# PE01.net
KiCad netlist of a schematic drawn in EAGLE
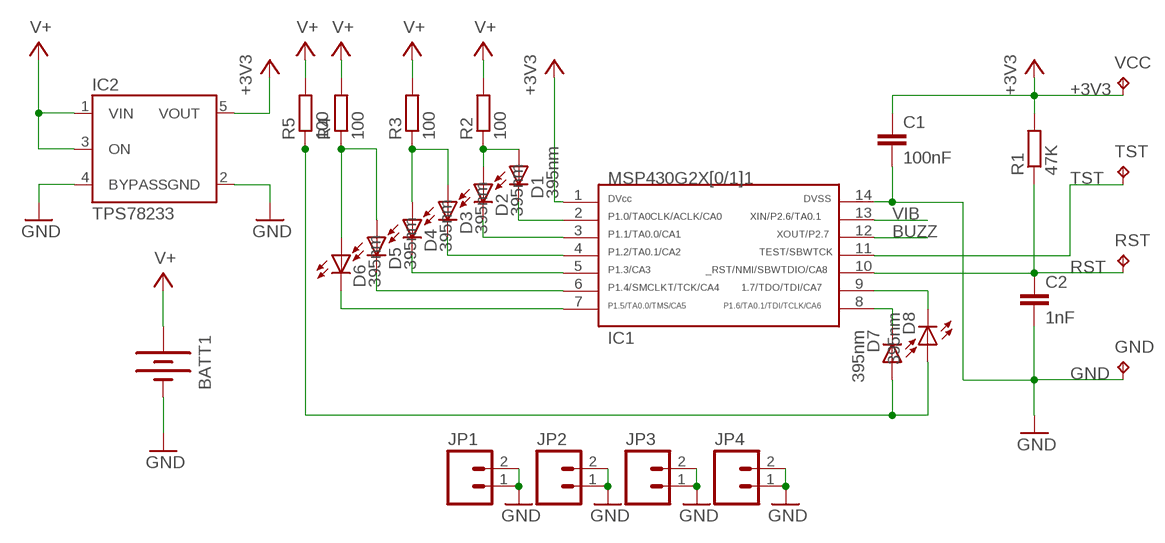
[diagram p0: schematic, sheet 1]

(export (version "E")
  (design (tool "Eeschema 10.0.6"))
  (components
    (comp (ref "BATT1")
      (value "BATTERY20MM_4LEGS")
      (footprint "eagle-import:BATTCON_20MM_4LEGS")
      (libsource (lib "eagle-import") (part "BATTERY20MM_4LEGS"))
    )
    (comp (ref "C1")
      (value "100nF")
      (footprint "eagle-import:0805")
      (libsource (lib "eagle-import") (part "CAP0805"))
    )
    (comp (ref "C2")
      (value "1nF")
      (footprint "eagle-import:0805")
      (libsource (lib "eagle-import") (part "CAP0805"))
    )
    (comp (ref "D1")
      (value "395nm")
      (footprint "eagle-import:LED-805")
      (libsource (lib "eagle-import") (part "LED-0805"))
    )
    (comp (ref "D2")
      (value "395nm")
      (footprint "eagle-import:LED-805")
      (libsource (lib "eagle-import") (part "LED-0805"))
    )
    (comp (ref "D3")
      (value "395nm")
      (footprint "eagle-import:LED-805")
      (libsource (lib "eagle-import") (part "LED-0805"))
    )
    (comp (ref "D4")
      (value "395nm")
      (footprint "eagle-import:LED-805")
      (libsource (lib "eagle-import") (part "LED-0805"))
    )
    (comp (ref "D5")
      (value "395nm")
      (footprint "eagle-import:LED-805")
      (libsource (lib "eagle-import") (part "LED-0805"))
    )
    (comp (ref "D6")
      (value "395nm")
      (footprint "eagle-import:LED-805")
      (libsource (lib "eagle-import") (part "LED-0805"))
    )
    (comp (ref "D7")
      (value "395nm")
      (footprint "eagle-import:LED-805")
      (libsource (lib "eagle-import") (part "LED-0805"))
    )
    (comp (ref "D8")
      (value "395nm")
      (footprint "eagle-import:LED-805")
      (libsource (lib "eagle-import") (part "LED-0805"))
    )
    (comp (ref "GND")
      (value "TPTP10R")
      (footprint "eagle-import:TP10R")
      (libsource (lib "eagle-import") (part "TPTP10R"))
    )
    (comp (ref "IC1")
      (value "MSP430G2231")
      (footprint "eagle-import:PW14")
      (libsource (lib "eagle-import") (part "G2X[0/1]1---PW14"))
    )
    (comp (ref "IC2")
      (value "TPS78233")
      (footprint "eagle-import:SOT23-5")
      (libsource (lib "eagle-import") (part "LP2982M5"))
    )
    (comp (ref "JP1")
      (value "M021X02_NO_SILK")
      (footprint "eagle-import:1X02_NO_SILK")
      (libsource (lib "eagle-import") (part "M021X02_NO_SILK"))
    )
    (comp (ref "JP2")
      (value "M021X02_NO_SILK")
      (footprint "eagle-import:1X02_NO_SILK")
      (libsource (lib "eagle-import") (part "M021X02_NO_SILK"))
    )
    (comp (ref "JP3")
      (value "M021X02_NO_SILK")
      (footprint "eagle-import:1X02_NO_SILK")
      (libsource (lib "eagle-import") (part "M021X02_NO_SILK"))
    )
    (comp (ref "JP4")
      (value "M021X02_NO_SILK")
      (footprint "eagle-import:1X02_NO_SILK")
      (libsource (lib "eagle-import") (part "M021X02_NO_SILK"))
    )
    (comp (ref "R1")
      (value "47K")
      (footprint "eagle-import:R0603")
      (libsource (lib "eagle-import") (part "R-EU_R0603"))
    )
    (comp (ref "R2")
      (value "100")
      (footprint "eagle-import:R0603")
      (libsource (lib "eagle-import") (part "R-EU_R0603"))
    )
    (comp (ref "R3")
      (value "100")
      (footprint "eagle-import:R0603")
      (libsource (lib "eagle-import") (part "R-EU_R0603"))
    )
    (comp (ref "R4")
      (value "100")
      (footprint "eagle-import:R0603")
      (libsource (lib "eagle-import") (part "R-EU_R0603"))
    )
    (comp (ref "R5")
      (value "100")
      (footprint "eagle-import:R0603")
      (libsource (lib "eagle-import") (part "R-EU_R0603"))
    )
    (comp (ref "RST")
      (value "TPTP10R")
      (footprint "eagle-import:TP10R")
      (libsource (lib "eagle-import") (part "TPTP10R"))
    )
    (comp (ref "TST")
      (value "TPTP10R")
      (footprint "eagle-import:TP10R")
      (libsource (lib "eagle-import") (part "TPTP10R"))
    )
    (comp (ref "VCC")
      (value "TPTP10R")
      (footprint "eagle-import:TP10R")
      (libsource (lib "eagle-import") (part "TPTP10R"))
    )
  )
  (nets
    (net (code "1") (name "+3V3") (class "Default")
      (node (ref "C1") (pin "1") (pinfunction "1_1") (pintype "passive"))
      (node (ref "IC1") (pin "1") (pinfunction "1_1") (pintype "bidirectional"))
      (node (ref "IC2") (pin "5") (pinfunction "VOUT_5") (pintype "output"))
      (node (ref "R1") (pin "2") (pinfunction "2_2") (pintype "passive"))
      (node (ref "VCC") (pin "TP") (pinfunction "TP_TP") (pintype "input"))
    )
    (net (code "2") (name "/BUZZ") (class "Default")
      (node (ref "IC1") (pin "12") (pinfunction "12_12") (pintype "bidirectional"))
    )
    (net (code "3") (name "/RST") (class "Default")
      (node (ref "C2") (pin "1") (pinfunction "1_1") (pintype "passive"))
      (node (ref "IC1") (pin "10") (pinfunction "10_10") (pintype "bidirectional"))
      (node (ref "R1") (pin "1") (pinfunction "1_1") (pintype "passive"))
      (node (ref "RST") (pin "TP") (pinfunction "TP_TP") (pintype "input"))
    )
    (net (code "4") (name "/TST") (class "Default")
      (node (ref "IC1") (pin "11") (pinfunction "11_11") (pintype "bidirectional"))
      (node (ref "TST") (pin "TP") (pinfunction "TP_TP") (pintype "input"))
    )
    (net (code "5") (name "/VIB") (class "Default")
      (node (ref "IC1") (pin "13") (pinfunction "13_13") (pintype "bidirectional"))
    )
    (net (code "6") (name "GND") (class "Default")
      (node (ref "BATT1") (pin "2") (pinfunction "-_2") (pintype "power_in"))
      (node (ref "C1") (pin "2") (pinfunction "2_2") (pintype "passive"))
      (node (ref "C2") (pin "2") (pinfunction "2_2") (pintype "passive"))
      (node (ref "GND") (pin "TP") (pinfunction "TP_TP") (pintype "input"))
      (node (ref "IC1") (pin "14") (pinfunction "14_14") (pintype "bidirectional"))
      (node (ref "IC2") (pin "2") (pinfunction "GND_2") (pintype "power_in"))
      (node (ref "IC2") (pin "4") (pinfunction "BYPASS_4") (pintype "passive"))
      (node (ref "JP1") (pin "1") (pinfunction "1_1") (pintype "passive"))
      (node (ref "JP1") (pin "2") (pinfunction "2_2") (pintype "passive"))
      (node (ref "JP2") (pin "1") (pinfunction "1_1") (pintype "passive"))
      (node (ref "JP2") (pin "2") (pinfunction "2_2") (pintype "passive"))
      (node (ref "JP3") (pin "1") (pinfunction "1_1") (pintype "passive"))
      (node (ref "JP3") (pin "2") (pinfunction "2_2") (pintype "passive"))
      (node (ref "JP4") (pin "1") (pinfunction "1_1") (pintype "passive"))
      (node (ref "JP4") (pin "2") (pinfunction "2_2") (pintype "passive"))
    )
    (net (code "7") (name "Net-(D1-PadA)") (class "Default")
      (node (ref "D1") (pin "A") (pinfunction "A_A") (pintype "passive"))
      (node (ref "D2") (pin "A") (pinfunction "A_A") (pintype "passive"))
      (node (ref "R2") (pin "1") (pinfunction "1_1") (pintype "passive"))
    )
    (net (code "8") (name "Net-(D1-PadC)") (class "Default")
      (node (ref "D1") (pin "C") (pinfunction "C_C") (pintype "passive"))
      (node (ref "IC1") (pin "2") (pinfunction "2_2") (pintype "bidirectional"))
    )
    (net (code "9") (name "Net-(D2-PadC)") (class "Default")
      (node (ref "D2") (pin "C") (pinfunction "C_C") (pintype "passive"))
      (node (ref "IC1") (pin "3") (pinfunction "3_3") (pintype "bidirectional"))
    )
    (net (code "10") (name "Net-(D3-PadA)") (class "Default")
      (node (ref "D3") (pin "A") (pinfunction "A_A") (pintype "passive"))
      (node (ref "D4") (pin "A") (pinfunction "A_A") (pintype "passive"))
      (node (ref "R3") (pin "1") (pinfunction "1_1") (pintype "passive"))
    )
    (net (code "11") (name "Net-(D3-PadC)") (class "Default")
      (node (ref "D3") (pin "C") (pinfunction "C_C") (pintype "passive"))
      (node (ref "IC1") (pin "4") (pinfunction "4_4") (pintype "bidirectional"))
    )
    (net (code "12") (name "Net-(D4-PadC)") (class "Default")
      (node (ref "D4") (pin "C") (pinfunction "C_C") (pintype "passive"))
      (node (ref "IC1") (pin "5") (pinfunction "5_5") (pintype "bidirectional"))
    )
    (net (code "13") (name "Net-(D5-PadA)") (class "Default")
      (node (ref "D5") (pin "A") (pinfunction "A_A") (pintype "passive"))
      (node (ref "D6") (pin "A") (pinfunction "A_A") (pintype "passive"))
      (node (ref "R4") (pin "1") (pinfunction "1_1") (pintype "passive"))
    )
    (net (code "14") (name "Net-(D5-PadC)") (class "Default")
      (node (ref "D5") (pin "C") (pinfunction "C_C") (pintype "passive"))
      (node (ref "IC1") (pin "6") (pinfunction "6_6") (pintype "bidirectional"))
    )
    (net (code "15") (name "Net-(D6-PadC)") (class "Default")
      (node (ref "D6") (pin "C") (pinfunction "C_C") (pintype "passive"))
      (node (ref "IC1") (pin "7") (pinfunction "7_7") (pintype "bidirectional"))
    )
    (net (code "16") (name "Net-(D7-PadA)") (class "Default")
      (node (ref "D7") (pin "A") (pinfunction "A_A") (pintype "passive"))
      (node (ref "D8") (pin "A") (pinfunction "A_A") (pintype "passive"))
      (node (ref "R5") (pin "1") (pinfunction "1_1") (pintype "passive"))
    )
    (net (code "17") (name "Net-(D7-PadC)") (class "Default")
      (node (ref "D7") (pin "C") (pinfunction "C_C") (pintype "passive"))
      (node (ref "IC1") (pin "8") (pinfunction "8_8") (pintype "bidirectional"))
    )
    (net (code "18") (name "Net-(D8-PadC)") (class "Default")
      (node (ref "D8") (pin "C") (pinfunction "C_C") (pintype "passive"))
      (node (ref "IC1") (pin "9") (pinfunction "9_9") (pintype "bidirectional"))
    )
    (net (code "19") (name "V+") (class "Default")
      (node (ref "BATT1") (pin "1") (pinfunction "+_1") (pintype "power_in"))
      (node (ref "IC2") (pin "1") (pinfunction "VIN_1") (pintype "power_in"))
      (node (ref "IC2") (pin "3") (pinfunction "ON_3") (pintype "input"))
      (node (ref "R2") (pin "2") (pinfunction "2_2") (pintype "passive"))
      (node (ref "R3") (pin "2") (pinfunction "2_2") (pintype "passive"))
      (node (ref "R4") (pin "2") (pinfunction "2_2") (pintype "passive"))
      (node (ref "R5") (pin "2") (pinfunction "2_2") (pintype "passive"))
    )
  )
)
